# 9xVoice_MikeB_SMD_v1_0b.net
KiCad netlist of a schematic drawn in EAGLE
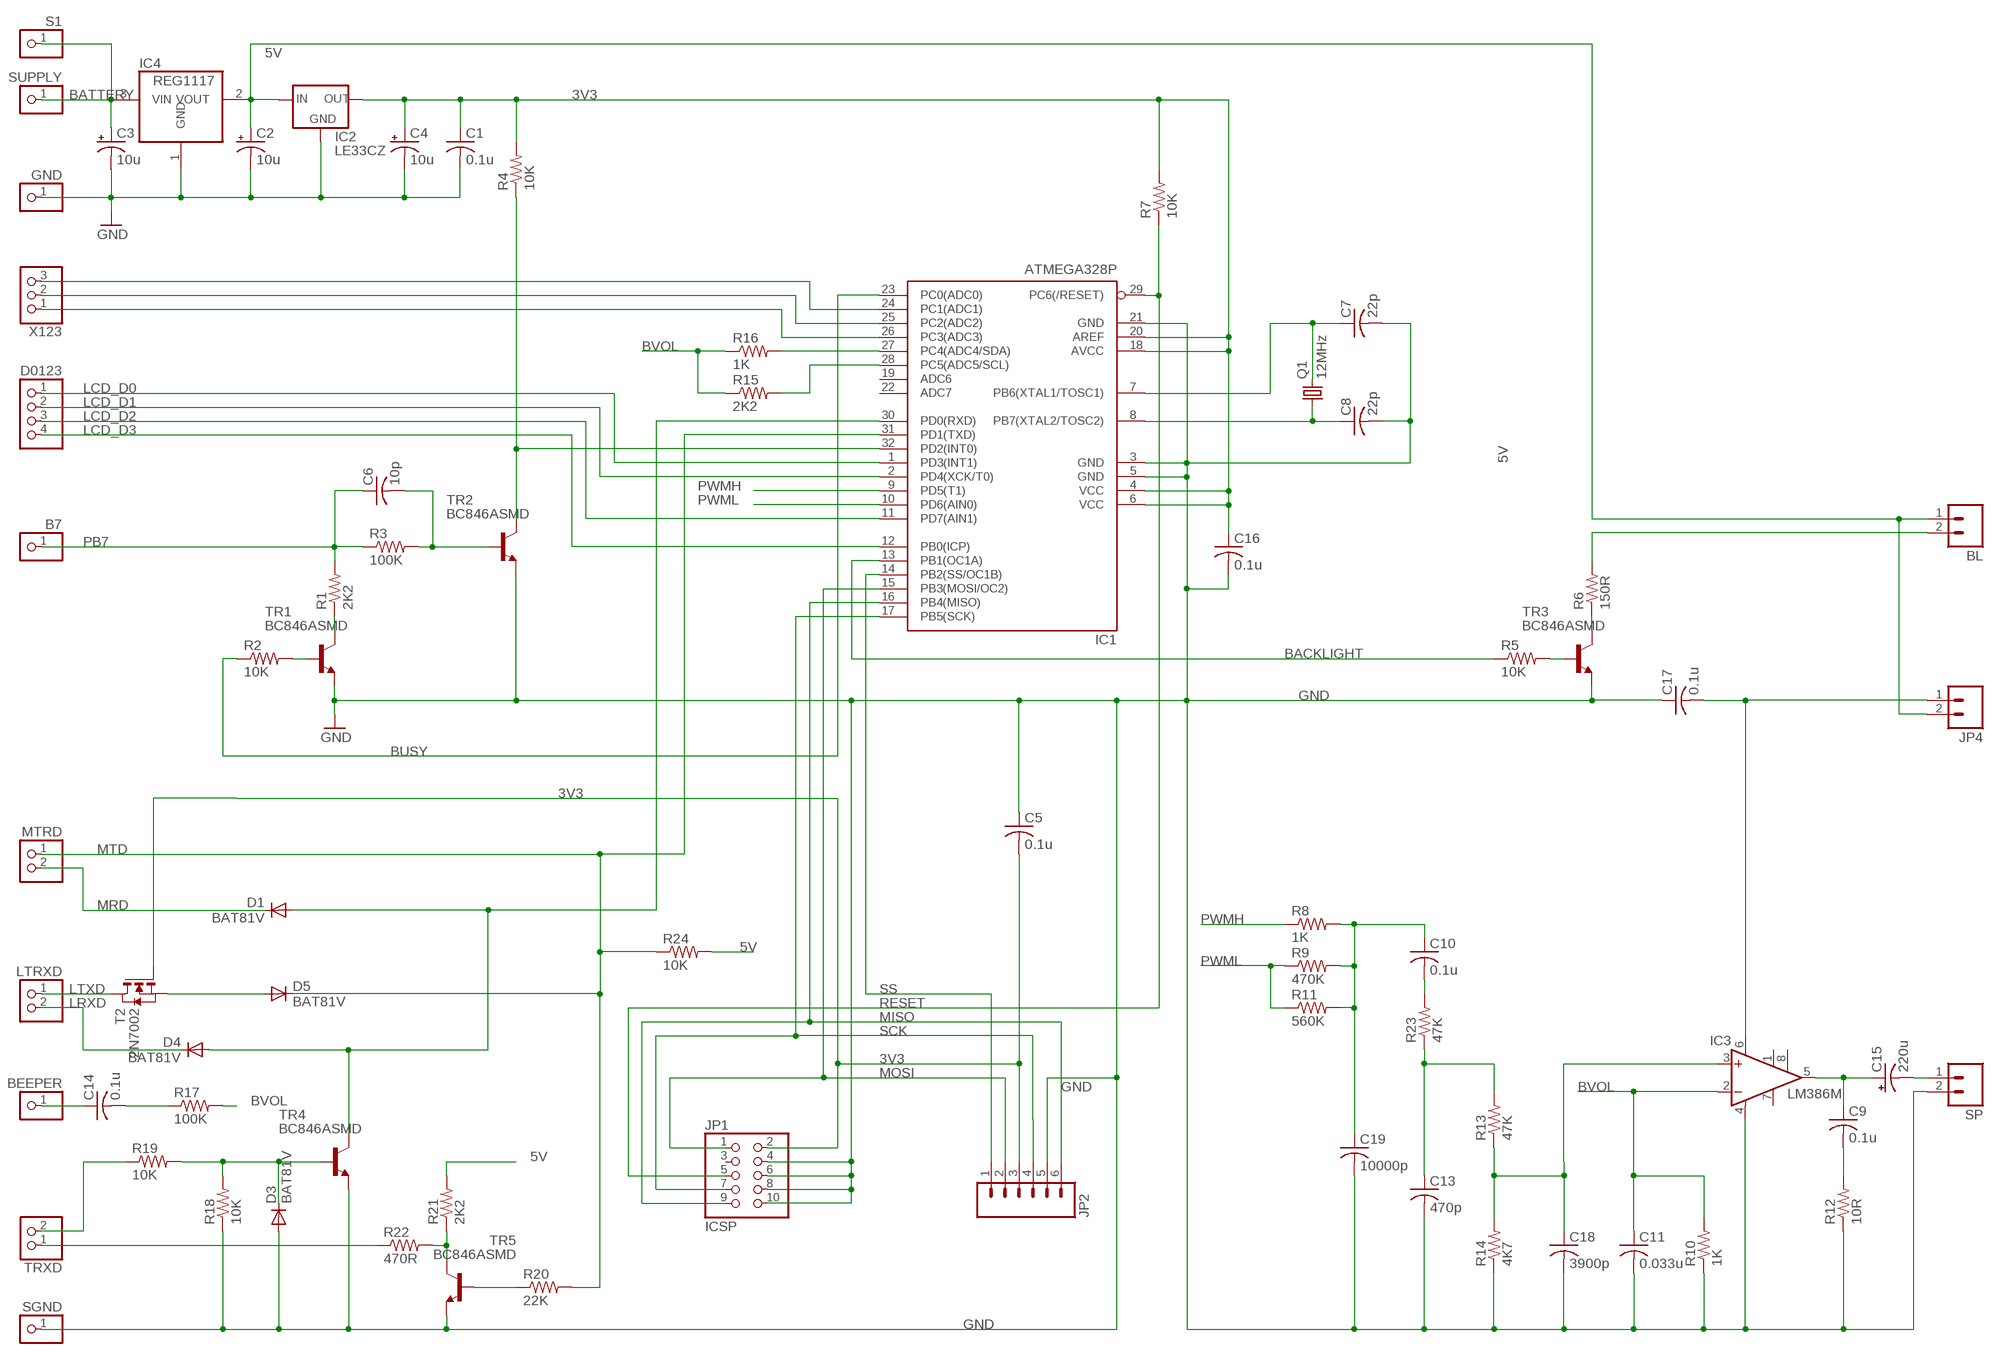
[diagram p0: schematic, sheet 1]

(export (version "E")
  (design (tool "Eeschema 10.0.6"))
  (components
    (comp (ref "B7")
      (value "PINHD-1X1")
      (footprint "eagle-import:1X01")
      (libsource (lib "eagle-import") (part "PINHD-1X1"))
    )
    (comp (ref "BEEPER")
      (value "PINHD-1X1")
      (footprint "eagle-import:1X01")
      (libsource (lib "eagle-import") (part "PINHD-1X1"))
    )
    (comp (ref "BL")
      (value "M02PTH")
      (footprint "eagle-import:1X02")
      (libsource (lib "eagle-import") (part "M02PTH"))
    )
    (comp (ref "C1")
      (value "0.1u")
      (footprint "eagle-import:C1206")
      (libsource (lib "eagle-import") (part "C-USC1206"))
    )
    (comp (ref "C2")
      (value "10u")
      (footprint "eagle-import:A_3216-18R")
      (libsource (lib "eagle-import") (part "CPOL-USA/3216-18R"))
    )
    (comp (ref "C3")
      (value "10u")
      (footprint "eagle-import:A_3216-18R")
      (libsource (lib "eagle-import") (part "CPOL-USA/3216-18R"))
    )
    (comp (ref "C4")
      (value "10u")
      (footprint "eagle-import:A_3216-18R")
      (libsource (lib "eagle-import") (part "CPOL-USA/3216-18R"))
    )
    (comp (ref "C5")
      (value "0.1u")
      (footprint "eagle-import:C1206")
      (libsource (lib "eagle-import") (part "C-USC1206"))
    )
    (comp (ref "C6")
      (value "10p")
      (footprint "eagle-import:C1206")
      (libsource (lib "eagle-import") (part "C-USC1206"))
    )
    (comp (ref "C7")
      (value "22p")
      (footprint "eagle-import:C1206")
      (libsource (lib "eagle-import") (part "C-USC1206"))
    )
    (comp (ref "C8")
      (value "22p")
      (footprint "eagle-import:C1206")
      (libsource (lib "eagle-import") (part "C-USC1206"))
    )
    (comp (ref "C9")
      (value "0.1u")
      (footprint "eagle-import:C1206")
      (libsource (lib "eagle-import") (part "C-USC1206"))
    )
    (comp (ref "C10")
      (value "0.1u")
      (footprint "eagle-import:C1206")
      (libsource (lib "eagle-import") (part "C-USC1206"))
    )
    (comp (ref "C11")
      (value "0.033u")
      (footprint "eagle-import:C1206")
      (libsource (lib "eagle-import") (part "C-USC1206"))
    )
    (comp (ref "C13")
      (value "470p")
      (footprint "eagle-import:C1206")
      (libsource (lib "eagle-import") (part "C-USC1206"))
    )
    (comp (ref "C14")
      (value "0.1u")
      (footprint "eagle-import:C1206")
      (libsource (lib "eagle-import") (part "C-USC1206"))
    )
    (comp (ref "C15")
      (value "220u")
      (footprint "eagle-import:CT7343")
      (libsource (lib "eagle-import") (part "CPOL-USCT7343"))
    )
    (comp (ref "C16")
      (value "0.1u")
      (footprint "eagle-import:C1206")
      (libsource (lib "eagle-import") (part "C-USC1206"))
    )
    (comp (ref "C17")
      (value "0.1u")
      (footprint "eagle-import:C1206")
      (libsource (lib "eagle-import") (part "C-USC1206"))
    )
    (comp (ref "C18")
      (value "3900p")
      (footprint "eagle-import:C1206")
      (libsource (lib "eagle-import") (part "C-USC1206"))
    )
    (comp (ref "C19")
      (value "10000p")
      (footprint "eagle-import:C1206")
      (libsource (lib "eagle-import") (part "C-USC1206"))
    )
    (comp (ref "D1")
      (value "BAT81V")
      (footprint "eagle-import:SOD123")
      (libsource (lib "eagle-import") (part "DIODE-SOD123"))
    )
    (comp (ref "D3")
      (value "BAT81V")
      (footprint "eagle-import:SOD123")
      (libsource (lib "eagle-import") (part "DIODE-SOD123"))
    )
    (comp (ref "D4")
      (value "BAT81V")
      (footprint "eagle-import:SOD123")
      (libsource (lib "eagle-import") (part "DIODE-SOD123"))
    )
    (comp (ref "D5")
      (value "BAT81V")
      (footprint "eagle-import:SOD123")
      (libsource (lib "eagle-import") (part "DIODE-SOD123"))
    )
    (comp (ref "D0123")
      (value "PINHD-1X4")
      (footprint "eagle-import:1X04")
      (libsource (lib "eagle-import") (part "PINHD-1X4"))
    )
    (comp (ref "GND")
      (value "PINHD-1X1")
      (footprint "eagle-import:1X01")
      (libsource (lib "eagle-import") (part "PINHD-1X1"))
    )
    (comp (ref "IC1")
      (value "ATMEGA328P")
      (footprint "eagle-import:TQFP32-08")
      (fields
        (field (name "MPN") "ATMEGA8-16AU")
        (field (name "MPN_1") "ATMEGA8-16AU")
        (field (name "OC_FARNELL") "9171371")
        (field (name "OC_NEWARK") "73M8863")
      )
      (libsource (lib "eagle-import") (part "MEGA8-AI"))
    )
    (comp (ref "IC2")
      (value "LE33CZ")
      (footprint "eagle-import:SOT23")
      (libsource (lib "eagle-import") (part "XC63FPM"))
    )
    (comp (ref "IC3")
      (value "LM386M")
      (footprint "eagle-import:SO08")
      (libsource (lib "eagle-import") (part "LM386?-M1"))
    )
    (comp (ref "IC4")
      (value "REG1117")
      (footprint "eagle-import:SOT223")
      (libsource (lib "eagle-import") (part "REG1117"))
    )
    (comp (ref "JP1")
      (value "ICSP")
      (footprint "eagle-import:2X05")
      (libsource (lib "eagle-import") (part "PINHD-2X5"))
    )
    (comp (ref "JP2")
      (value "M06SIP")
      (footprint "eagle-import:1X06")
      (libsource (lib "eagle-import") (part "M06SIP"))
    )
    (comp (ref "JP4")
      (value "M02PTH")
      (footprint "eagle-import:1X02")
      (libsource (lib "eagle-import") (part "M02PTH"))
    )
    (comp (ref "LTRXD")
      (value "PINHD-1X2")
      (footprint "eagle-import:1X02")
      (libsource (lib "eagle-import") (part "PINHD-1X2"))
    )
    (comp (ref "MTRD")
      (value "PINHD-1X2")
      (footprint "eagle-import:1X02")
      (libsource (lib "eagle-import") (part "PINHD-1X2"))
    )
    (comp (ref "Q1")
      (value "12MHz")
      (footprint "eagle-import:2-SMD")
      (libsource (lib "eagle-import") (part "7A"))
    )
    (comp (ref "R1")
      (value "2K2")
      (footprint "eagle-import:R1206")
      (libsource (lib "eagle-import") (part "R-US_R1206"))
    )
    (comp (ref "R2")
      (value "10K")
      (footprint "eagle-import:R1206")
      (libsource (lib "eagle-import") (part "R-US_R1206"))
    )
    (comp (ref "R3")
      (value "100K")
      (footprint "eagle-import:R1206")
      (libsource (lib "eagle-import") (part "R-US_R1206"))
    )
    (comp (ref "R4")
      (value "10K")
      (footprint "eagle-import:R1206")
      (libsource (lib "eagle-import") (part "R-US_R1206"))
    )
    (comp (ref "R5")
      (value "10K")
      (footprint "eagle-import:R1206")
      (libsource (lib "eagle-import") (part "R-US_R1206"))
    )
    (comp (ref "R6")
      (value "150R")
      (footprint "eagle-import:R1206")
      (libsource (lib "eagle-import") (part "R-US_R1206"))
    )
    (comp (ref "R7")
      (value "10K")
      (footprint "eagle-import:R1206")
      (libsource (lib "eagle-import") (part "R-US_R1206"))
    )
    (comp (ref "R8")
      (value "1K")
      (footprint "eagle-import:R1206")
      (libsource (lib "eagle-import") (part "R-US_R1206"))
    )
    (comp (ref "R9")
      (value "470K")
      (footprint "eagle-import:R1206")
      (libsource (lib "eagle-import") (part "R-US_R1206"))
    )
    (comp (ref "R10")
      (value "1K")
      (footprint "eagle-import:R1206")
      (libsource (lib "eagle-import") (part "R-US_R1206"))
    )
    (comp (ref "R11")
      (value "560K")
      (footprint "eagle-import:R1206")
      (libsource (lib "eagle-import") (part "R-US_R1206"))
    )
    (comp (ref "R12")
      (value "10R")
      (footprint "eagle-import:R1206")
      (libsource (lib "eagle-import") (part "R-US_R1206"))
    )
    (comp (ref "R13")
      (value "47K")
      (footprint "eagle-import:R1206")
      (libsource (lib "eagle-import") (part "R-US_R1206"))
    )
    (comp (ref "R14")
      (value "4K7")
      (footprint "eagle-import:R1206")
      (libsource (lib "eagle-import") (part "R-US_R1206"))
    )
    (comp (ref "R15")
      (value "2K2")
      (footprint "eagle-import:R1206")
      (libsource (lib "eagle-import") (part "R-US_R1206"))
    )
    (comp (ref "R16")
      (value "1K")
      (footprint "eagle-import:R1206")
      (libsource (lib "eagle-import") (part "R-US_R1206"))
    )
    (comp (ref "R17")
      (value "100K")
      (footprint "eagle-import:R1206")
      (libsource (lib "eagle-import") (part "R-US_R1206"))
    )
    (comp (ref "R18")
      (value "10K")
      (footprint "eagle-import:R1206")
      (libsource (lib "eagle-import") (part "R-US_R1206"))
    )
    (comp (ref "R19")
      (value "10K")
      (footprint "eagle-import:R1206")
      (libsource (lib "eagle-import") (part "R-US_R1206"))
    )
    (comp (ref "R20")
      (value "22K")
      (footprint "eagle-import:R1206")
      (libsource (lib "eagle-import") (part "R-US_R1206"))
    )
    (comp (ref "R21")
      (value "2K2")
      (footprint "eagle-import:R1206")
      (libsource (lib "eagle-import") (part "R-US_R1206"))
    )
    (comp (ref "R22")
      (value "470R")
      (footprint "eagle-import:R1206")
      (libsource (lib "eagle-import") (part "R-US_R1206"))
    )
    (comp (ref "R23")
      (value "47K")
      (footprint "eagle-import:R1206")
      (libsource (lib "eagle-import") (part "R-US_R1206"))
    )
    (comp (ref "R24")
      (value "10K")
      (footprint "eagle-import:R1206")
      (libsource (lib "eagle-import") (part "R-US_R1206"))
    )
    (comp (ref "S1")
      (value "PINHD-1X1")
      (footprint "eagle-import:1X01")
      (libsource (lib "eagle-import") (part "PINHD-1X1"))
    )
    (comp (ref "SGND")
      (value "PINHD-1X1")
      (footprint "eagle-import:1X01")
      (libsource (lib "eagle-import") (part "PINHD-1X1"))
    )
    (comp (ref "SP")
      (value "M02PTH")
      (footprint "eagle-import:1X02")
      (libsource (lib "eagle-import") (part "M02PTH"))
    )
    (comp (ref "SUPPLY")
      (value "PINHD-1X1")
      (footprint "eagle-import:1X01")
      (libsource (lib "eagle-import") (part "PINHD-1X1"))
    )
    (comp (ref "T2")
      (value "2N7002")
      (footprint "eagle-import:SOT-23")
      (libsource (lib "eagle-import") (part "NMOSSOT23"))
    )
    (comp (ref "TR1")
      (value "BC846ASMD")
      (footprint "eagle-import:SOT23")
      (libsource (lib "eagle-import") (part "BC846SMDA"))
    )
    (comp (ref "TR2")
      (value "BC846ASMD")
      (footprint "eagle-import:SOT23")
      (libsource (lib "eagle-import") (part "BC846SMDA"))
    )
    (comp (ref "TR3")
      (value "BC846ASMD")
      (footprint "eagle-import:SOT23")
      (libsource (lib "eagle-import") (part "BC846SMDA"))
    )
    (comp (ref "TR4")
      (value "BC846ASMD")
      (footprint "eagle-import:SOT23")
      (libsource (lib "eagle-import") (part "BC846SMDA"))
    )
    (comp (ref "TR5")
      (value "BC846ASMD")
      (footprint "eagle-import:SOT23")
      (libsource (lib "eagle-import") (part "BC846SMDA"))
    )
    (comp (ref "TRXD")
      (value "PINHD-1X2")
      (footprint "eagle-import:1X02")
      (libsource (lib "eagle-import") (part "PINHD-1X2"))
    )
    (comp (ref "X123")
      (value "PINHD-1X3")
      (footprint "eagle-import:1X03")
      (libsource (lib "eagle-import") (part "PINHD-1X3"))
    )
  )
  (nets
    (net (code "1") (name "/3V3") (class "Default")
      (node (ref "C1") (pin "1") (pinfunction "1_1") (pintype "passive"))
      (node (ref "C16") (pin "1") (pinfunction "1_1") (pintype "passive"))
      (node (ref "C4") (pin "+") (pinfunction "+_+") (pintype "passive"))
      (node (ref "C5") (pin "2") (pinfunction "2_2") (pintype "passive"))
      (node (ref "IC1") (pin "18") (pinfunction "AVCC_18") (pintype "power_in"))
      (node (ref "IC1") (pin "20") (pinfunction "AREF_20") (pintype "passive"))
      (node (ref "IC1") (pin "4") (pinfunction "VCC_4") (pintype "power_in"))
      (node (ref "IC1") (pin "6") (pinfunction "VCC_6") (pintype "power_in"))
      (node (ref "IC2") (pin "2") (pinfunction "OUT_2") (pintype "passive"))
      (node (ref "JP1") (pin "2") (pinfunction "2_2") (pintype "passive"))
      (node (ref "JP2") (pin "3") (pinfunction "3_3") (pintype "passive"))
      (node (ref "R4") (pin "2") (pinfunction "2_2") (pintype "passive"))
      (node (ref "R7") (pin "2") (pinfunction "2_2") (pintype "passive"))
      (node (ref "T2") (pin "3") (pinfunction "G_3") (pintype "passive"))
    )
    (net (code "2") (name "/5V") (class "Default")
      (node (ref "BL") (pin "1") (pinfunction "1_1") (pintype "passive"))
      (node (ref "C2") (pin "+") (pinfunction "+_+") (pintype "passive"))
      (node (ref "IC2") (pin "3") (pinfunction "IN_3") (pintype "input"))
      (node (ref "IC4") (pin "2") (pinfunction "VOUT_2") (pintype "output"))
      (node (ref "JP4") (pin "2") (pinfunction "2_2") (pintype "passive"))
      (node (ref "R21") (pin "2") (pinfunction "2_2") (pintype "passive"))
      (node (ref "R24") (pin "2") (pinfunction "2_2") (pintype "passive"))
    )
    (net (code "3") (name "/BACKLIGHT") (class "Default")
      (node (ref "IC1") (pin "13") (pinfunction "PB1(OC1A)_13") (pintype "bidirectional"))
      (node (ref "R5") (pin "1") (pinfunction "1_1") (pintype "passive"))
    )
    (net (code "4") (name "/BATTERY") (class "Default")
      (node (ref "C3") (pin "+") (pinfunction "+_+") (pintype "passive"))
      (node (ref "IC4") (pin "3") (pinfunction "VIN_3") (pintype "input"))
      (node (ref "S1") (pin "1") (pinfunction "1_1") (pintype "passive"))
      (node (ref "SUPPLY") (pin "1") (pinfunction "1_1") (pintype "passive"))
    )
    (net (code "5") (name "/BUSY") (class "Default")
      (node (ref "IC1") (pin "23") (pinfunction "PC0(ADC0)_23") (pintype "bidirectional"))
      (node (ref "R2") (pin "1") (pinfunction "1_1") (pintype "passive"))
    )
    (net (code "6") (name "/BVOL") (class "Default")
      (node (ref "C11") (pin "1") (pinfunction "1_1") (pintype "passive"))
      (node (ref "IC3") (pin "2") (pinfunction "-IN_2") (pintype "input"))
      (node (ref "R10") (pin "2") (pinfunction "2_2") (pintype "passive"))
      (node (ref "R15") (pin "1") (pinfunction "1_1") (pintype "passive"))
      (node (ref "R16") (pin "1") (pinfunction "1_1") (pintype "passive"))
      (node (ref "R17") (pin "2") (pinfunction "2_2") (pintype "passive"))
    )
    (net (code "7") (name "/LCD_D0") (class "Default")
      (node (ref "D0123") (pin "1") (pinfunction "1_1") (pintype "passive"))
      (node (ref "IC1") (pin "1") (pinfunction "PD3(INT1)_1") (pintype "bidirectional"))
    )
    (net (code "8") (name "/LCD_D1") (class "Default")
      (node (ref "D0123") (pin "2") (pinfunction "2_2") (pintype "passive"))
      (node (ref "IC1") (pin "2") (pinfunction "PD4(XCK/T0)_2") (pintype "bidirectional"))
    )
    (net (code "9") (name "/LCD_D2") (class "Default")
      (node (ref "D0123") (pin "3") (pinfunction "3_3") (pintype "passive"))
      (node (ref "IC1") (pin "11") (pinfunction "PD7(AIN1)_11") (pintype "bidirectional"))
    )
    (net (code "10") (name "/LCD_D3") (class "Default")
      (node (ref "D0123") (pin "4") (pinfunction "4_4") (pintype "passive"))
      (node (ref "IC1") (pin "12") (pinfunction "PB0(ICP)_12") (pintype "bidirectional"))
    )
    (net (code "11") (name "/LRXD") (class "Default")
      (node (ref "D4") (pin "C") (pinfunction "C_C") (pintype "passive"))
      (node (ref "LTRXD") (pin "2") (pinfunction "2_2") (pintype "passive"))
    )
    (net (code "12") (name "/LTXD") (class "Default")
      (node (ref "LTRXD") (pin "1") (pinfunction "1_1") (pintype "passive"))
      (node (ref "T2") (pin "1") (pinfunction "D_1") (pintype "passive"))
    )
    (net (code "13") (name "/MISO") (class "Default")
      (node (ref "IC1") (pin "16") (pinfunction "PB4(MISO)_16") (pintype "bidirectional"))
      (node (ref "JP1") (pin "9") (pinfunction "9_9") (pintype "passive"))
      (node (ref "JP2") (pin "6") (pinfunction "6_6") (pintype "passive"))
    )
    (net (code "14") (name "/MOSI") (class "Default")
      (node (ref "IC1") (pin "15") (pinfunction "PB3(MOSI/OC2)_15") (pintype "bidirectional"))
      (node (ref "JP1") (pin "1") (pinfunction "1_1") (pintype "passive"))
      (node (ref "JP2") (pin "2") (pinfunction "2_2") (pintype "passive"))
    )
    (net (code "15") (name "/MRD") (class "Default")
      (node (ref "D1") (pin "C") (pinfunction "C_C") (pintype "passive"))
      (node (ref "MTRD") (pin "2") (pinfunction "2_2") (pintype "passive"))
    )
    (net (code "16") (name "/MTD") (class "Default")
      (node (ref "D5") (pin "C") (pinfunction "C_C") (pintype "passive"))
      (node (ref "IC1") (pin "31") (pinfunction "PD1(TXD)_31") (pintype "bidirectional"))
      (node (ref "MTRD") (pin "1") (pinfunction "1_1") (pintype "passive"))
      (node (ref "R20") (pin "2") (pinfunction "2_2") (pintype "passive"))
      (node (ref "R24") (pin "1") (pinfunction "1_1") (pintype "passive"))
    )
    (net (code "17") (name "/PB7") (class "Default")
      (node (ref "B7") (pin "1") (pinfunction "1_1") (pintype "passive"))
      (node (ref "C6") (pin "1") (pinfunction "1_1") (pintype "passive"))
      (node (ref "R1") (pin "2") (pinfunction "2_2") (pintype "passive"))
      (node (ref "R3") (pin "1") (pinfunction "1_1") (pintype "passive"))
    )
    (net (code "18") (name "/PWMH") (class "Default")
      (node (ref "IC1") (pin "9") (pinfunction "PD5(T1)_9") (pintype "bidirectional"))
      (node (ref "R8") (pin "1") (pinfunction "1_1") (pintype "passive"))
    )
    (net (code "19") (name "/PWML") (class "Default")
      (node (ref "IC1") (pin "10") (pinfunction "PD6(AIN0)_10") (pintype "bidirectional"))
      (node (ref "R11") (pin "1") (pinfunction "1_1") (pintype "passive"))
      (node (ref "R9") (pin "1") (pinfunction "1_1") (pintype "passive"))
    )
    (net (code "20") (name "/RESET") (class "Default")
      (node (ref "IC1") (pin "29") (pinfunction "PC6(/RESET)_29") (pintype "bidirectional"))
      (node (ref "JP1") (pin "5") (pinfunction "5_5") (pintype "passive"))
      (node (ref "R7") (pin "1") (pinfunction "1_1") (pintype "passive"))
    )
    (net (code "21") (name "/SCK") (class "Default")
      (node (ref "IC1") (pin "17") (pinfunction "PB5(SCK)_17") (pintype "bidirectional"))
      (node (ref "JP1") (pin "7") (pinfunction "7_7") (pintype "passive"))
      (node (ref "JP2") (pin "4") (pinfunction "4_4") (pintype "passive"))
    )
    (net (code "22") (name "/SS") (class "Default")
      (node (ref "IC1") (pin "14") (pinfunction "PB2(SS/OC1B)_14") (pintype "bidirectional"))
      (node (ref "JP2") (pin "1") (pinfunction "1_1") (pintype "passive"))
    )
    (net (code "23") (name "GND") (class "Default")
      (node (ref "C1") (pin "2") (pinfunction "2_2") (pintype "passive"))
      (node (ref "C11") (pin "2") (pinfunction "2_2") (pintype "passive"))
      (node (ref "C13") (pin "2") (pinfunction "2_2") (pintype "passive"))
      (node (ref "C16") (pin "2") (pinfunction "2_2") (pintype "passive"))
      (node (ref "C17") (pin "1") (pinfunction "1_1") (pintype "passive"))
      (node (ref "C18") (pin "2") (pinfunction "2_2") (pintype "passive"))
      (node (ref "C19") (pin "2") (pinfunction "2_2") (pintype "passive"))
      (node (ref "C2") (pin "-") (pinfunction "-_-") (pintype "passive"))
      (node (ref "C3") (pin "-") (pinfunction "-_-") (pintype "passive"))
      (node (ref "C4") (pin "-") (pinfunction "-_-") (pintype "passive"))
      (node (ref "C5") (pin "1") (pinfunction "1_1") (pintype "passive"))
      (node (ref "C7") (pin "2") (pinfunction "2_2") (pintype "passive"))
      (node (ref "C8") (pin "2") (pinfunction "2_2") (pintype "passive"))
      (node (ref "D3") (pin "A") (pinfunction "A_A") (pintype "passive"))
      (node (ref "GND") (pin "1") (pinfunction "1_1") (pintype "passive"))
      (node (ref "IC1") (pin "21") (pinfunction "GND_21") (pintype "power_in"))
      (node (ref "IC1") (pin "3") (pinfunction "GND_3") (pintype "power_in"))
      (node (ref "IC1") (pin "5") (pinfunction "GND_5") (pintype "power_in"))
      (node (ref "IC2") (pin "1") (pinfunction "GND_1") (pintype "input"))
      (node (ref "IC3") (pin "4") (pinfunction "GND_4") (pintype "power_in"))
      (node (ref "IC4") (pin "1") (pinfunction "GND_1") (pintype "power_in"))
      (node (ref "JP1") (pin "10") (pinfunction "10_10") (pintype "passive"))
      (node (ref "JP1") (pin "4") (pinfunction "4_4") (pintype "passive"))
      (node (ref "JP1") (pin "6") (pinfunction "6_6") (pintype "passive"))
      (node (ref "JP1") (pin "8") (pinfunction "8_8") (pintype "passive"))
      (node (ref "JP2") (pin "5") (pinfunction "5_5") (pintype "passive"))
      (node (ref "R10") (pin "1") (pinfunction "1_1") (pintype "passive"))
      (node (ref "R12") (pin "1") (pinfunction "1_1") (pintype "passive"))
      (node (ref "R14") (pin "1") (pinfunction "1_1") (pintype "passive"))
      (node (ref "R18") (pin "1") (pinfunction "1_1") (pintype "passive"))
      (node (ref "SGND") (pin "1") (pinfunction "1_1") (pintype "passive"))
      (node (ref "SP") (pin "2") (pinfunction "2_2") (pintype "passive"))
      (node (ref "TR1") (pin "2") (pinfunction "E_2") (pintype "passive"))
      (node (ref "TR2") (pin "2") (pinfunction "E_2") (pintype "passive"))
      (node (ref "TR3") (pin "2") (pinfunction "E_2") (pintype "passive"))
      (node (ref "TR4") (pin "2") (pinfunction "E_2") (pintype "passive"))
      (node (ref "TR5") (pin "2") (pinfunction "E_2") (pintype "passive"))
    )
    (net (code "24") (name "Net-(BEEPER-Pad1)") (class "Default")
      (node (ref "BEEPER") (pin "1") (pinfunction "1_1") (pintype "passive"))
      (node (ref "C14") (pin "1") (pinfunction "1_1") (pintype "passive"))
    )
    (net (code "25") (name "Net-(BL-Pad2)") (class "Default")
      (node (ref "BL") (pin "2") (pinfunction "2_2") (pintype "passive"))
      (node (ref "R6") (pin "2") (pinfunction "2_2") (pintype "passive"))
    )
    (net (code "26") (name "Net-(C9-Pad2)") (class "Default")
      (node (ref "C9") (pin "2") (pinfunction "2_2") (pintype "passive"))
      (node (ref "R12") (pin "2") (pinfunction "2_2") (pintype "passive"))
    )
    (net (code "27") (name "Net-(C10-Pad1)") (class "Default")
      (node (ref "C10") (pin "1") (pinfunction "1_1") (pintype "passive"))
      (node (ref "C19") (pin "1") (pinfunction "1_1") (pintype "passive"))
      (node (ref "R11") (pin "2") (pinfunction "2_2") (pintype "passive"))
      (node (ref "R8") (pin "2") (pinfunction "2_2") (pintype "passive"))
      (node (ref "R9") (pin "2") (pinfunction "2_2") (pintype "passive"))
    )
    (net (code "28") (name "Net-(C10-Pad2)") (class "Default")
      (node (ref "C10") (pin "2") (pinfunction "2_2") (pintype "passive"))
      (node (ref "R23") (pin "2") (pinfunction "2_2") (pintype "passive"))
    )
    (net (code "29") (name "Net-(C13-Pad1)") (class "Default")
      (node (ref "C13") (pin "1") (pinfunction "1_1") (pintype "passive"))
      (node (ref "R13") (pin "2") (pinfunction "2_2") (pintype "passive"))
      (node (ref "R23") (pin "1") (pinfunction "1_1") (pintype "passive"))
    )
    (net (code "30") (name "Net-(C14-Pad2)") (class "Default")
      (node (ref "C14") (pin "2") (pinfunction "2_2") (pintype "passive"))
      (node (ref "R17") (pin "1") (pinfunction "1_1") (pintype "passive"))
    )
    (net (code "31") (name "Net-(C15-Pad-)") (class "Default")
      (node (ref "C15") (pin "-") (pinfunction "-_-") (pintype "passive"))
      (node (ref "SP") (pin "1") (pinfunction "1_1") (pintype "passive"))
    )
    (net (code "32") (name "Net-(IC1-PB6(XTAL1{slash}TOSC1))") (class "Default")
      (node (ref "C7") (pin "1") (pinfunction "1_1") (pintype "passive"))
      (node (ref "IC1") (pin "7") (pinfunction "PB6(XTAL1/TOSC1)_7") (pintype "bidirectional"))
      (node (ref "Q1") (pin "P$2") (pinfunction "2_P$2") (pintype "passive"))
    )
    (net (code "33") (name "Net-(IC1-PB7(XTAL2{slash}TOSC2))") (class "Default")
      (node (ref "C8") (pin "1") (pinfunction "1_1") (pintype "passive"))
      (node (ref "IC1") (pin "8") (pinfunction "PB7(XTAL2/TOSC2)_8") (pintype "bidirectional"))
      (node (ref "Q1") (pin "P$1") (pinfunction "1_P$1") (pintype "passive"))
    )
    (net (code "34") (name "Net-(IC1-PC1(ADC1))") (class "Default")
      (node (ref "IC1") (pin "24") (pinfunction "PC1(ADC1)_24") (pintype "bidirectional"))
      (node (ref "X123") (pin "3") (pinfunction "3_3") (pintype "passive"))
    )
    (net (code "35") (name "Net-(IC1-PC2(ADC2))") (class "Default")
      (node (ref "IC1") (pin "25") (pinfunction "PC2(ADC2)_25") (pintype "bidirectional"))
      (node (ref "X123") (pin "2") (pinfunction "2_2") (pintype "passive"))
    )
    (net (code "36") (name "Net-(IC1-PC3(ADC3))") (class "Default")
      (node (ref "IC1") (pin "26") (pinfunction "PC3(ADC3)_26") (pintype "bidirectional"))
      (node (ref "X123") (pin "1") (pinfunction "1_1") (pintype "passive"))
    )
    (net (code "37") (name "Net-(IC1-PC4(ADC4{slash}SDA))") (class "Default")
      (node (ref "IC1") (pin "27") (pinfunction "PC4(ADC4/SDA)_27") (pintype "bidirectional"))
      (node (ref "R16") (pin "2") (pinfunction "2_2") (pintype "passive"))
    )
    (net (code "38") (name "Net-(IC1-PC5(ADC5{slash}SCL))") (class "Default")
      (node (ref "IC1") (pin "28") (pinfunction "PC5(ADC5/SCL)_28") (pintype "bidirectional"))
      (node (ref "R15") (pin "2") (pinfunction "2_2") (pintype "passive"))
    )
    (net (code "39") (name "Net-(IC1-PD0(RXD))") (class "Default")
      (node (ref "D1") (pin "A") (pinfunction "A_A") (pintype "passive"))
      (node (ref "D4") (pin "A") (pinfunction "A_A") (pintype "passive"))
      (node (ref "IC1") (pin "30") (pinfunction "PD0(RXD)_30") (pintype "bidirectional"))
      (node (ref "TR4") (pin "3") (pinfunction "C_3") (pintype "passive"))
    )
    (net (code "40") (name "Net-(IC1-PD2(INT0))") (class "Default")
      (node (ref "IC1") (pin "32") (pinfunction "PD2(INT0)_32") (pintype "bidirectional"))
      (node (ref "R4") (pin "1") (pinfunction "1_1") (pintype "passive"))
      (node (ref "TR2") (pin "3") (pinfunction "C_3") (pintype "passive"))
    )
    (net (code "41") (name "Net-(IC3-+IN)") (class "Default")
      (node (ref "C18") (pin "1") (pinfunction "1_1") (pintype "passive"))
      (node (ref "IC3") (pin "3") (pinfunction "+IN_3") (pintype "input"))
      (node (ref "R13") (pin "1") (pinfunction "1_1") (pintype "passive"))
      (node (ref "R14") (pin "2") (pinfunction "2_2") (pintype "passive"))
    )
    (net (code "42") (name "Net-(IC3-OUT)") (class "Default")
      (node (ref "C15") (pin "+") (pinfunction "+_+") (pintype "passive"))
      (node (ref "C9") (pin "1") (pinfunction "1_1") (pintype "passive"))
      (node (ref "IC3") (pin "5") (pinfunction "OUT_5") (pintype "output"))
    )
    (net (code "43") (name "Net-(IC3-VS)") (class "Default")
      (node (ref "C17") (pin "2") (pinfunction "2_2") (pintype "passive"))
      (node (ref "IC3") (pin "6") (pinfunction "VS_6") (pintype "power_in"))
      (node (ref "JP4") (pin "1") (pinfunction "1_1") (pintype "passive"))
    )
    (net (code "44") (name "Net-(R19-Pad1)") (class "Default")
      (node (ref "R19") (pin "1") (pinfunction "1_1") (pintype "passive"))
      (node (ref "TRXD") (pin "2") (pinfunction "2_2") (pintype "passive"))
    )
    (net (code "45") (name "Net-(R22-Pad1)") (class "Default")
      (node (ref "R22") (pin "1") (pinfunction "1_1") (pintype "passive"))
      (node (ref "TRXD") (pin "1") (pinfunction "1_1") (pintype "passive"))
    )
    (net (code "46") (name "Net-(T2-S)") (class "Default")
      (node (ref "D5") (pin "A") (pinfunction "A_A") (pintype "passive"))
      (node (ref "T2") (pin "2") (pinfunction "S_2") (pintype "passive"))
    )
    (net (code "47") (name "Net-(TR1-B)") (class "Default")
      (node (ref "R2") (pin "2") (pinfunction "2_2") (pintype "passive"))
      (node (ref "TR1") (pin "1") (pinfunction "B_1") (pintype "passive"))
    )
    (net (code "48") (name "Net-(TR1-C)") (class "Default")
      (node (ref "R1") (pin "1") (pinfunction "1_1") (pintype "passive"))
      (node (ref "TR1") (pin "3") (pinfunction "C_3") (pintype "passive"))
    )
    (net (code "49") (name "Net-(TR2-B)") (class "Default")
      (node (ref "C6") (pin "2") (pinfunction "2_2") (pintype "passive"))
      (node (ref "R3") (pin "2") (pinfunction "2_2") (pintype "passive"))
      (node (ref "TR2") (pin "1") (pinfunction "B_1") (pintype "passive"))
    )
    (net (code "50") (name "Net-(TR3-B)") (class "Default")
      (node (ref "R5") (pin "2") (pinfunction "2_2") (pintype "passive"))
      (node (ref "TR3") (pin "1") (pinfunction "B_1") (pintype "passive"))
    )
    (net (code "51") (name "Net-(TR3-C)") (class "Default")
      (node (ref "R6") (pin "1") (pinfunction "1_1") (pintype "passive"))
      (node (ref "TR3") (pin "3") (pinfunction "C_3") (pintype "passive"))
    )
    (net (code "52") (name "Net-(TR4-B)") (class "Default")
      (node (ref "D3") (pin "C") (pinfunction "C_C") (pintype "passive"))
      (node (ref "R18") (pin "2") (pinfunction "2_2") (pintype "passive"))
      (node (ref "R19") (pin "2") (pinfunction "2_2") (pintype "passive"))
      (node (ref "TR4") (pin "1") (pinfunction "B_1") (pintype "passive"))
    )
    (net (code "53") (name "Net-(TR5-B)") (class "Default")
      (node (ref "R20") (pin "1") (pinfunction "1_1") (pintype "passive"))
      (node (ref "TR5") (pin "1") (pinfunction "B_1") (pintype "passive"))
    )
    (net (code "54") (name "Net-(TR5-C)") (class "Default")
      (node (ref "R21") (pin "1") (pinfunction "1_1") (pintype "passive"))
      (node (ref "R22") (pin "2") (pinfunction "2_2") (pintype "passive"))
      (node (ref "TR5") (pin "3") (pinfunction "C_3") (pintype "passive"))
    )
    (net (code "55") (name "unconnected-(IC1-ADC6-Pad19)") (class "Default")
      (node (ref "IC1") (pin "19") (pinfunction "ADC6_19") (pintype "bidirectional"))
    )
    (net (code "56") (name "unconnected-(IC1-ADC7-Pad22)") (class "Default")
      (node (ref "IC1") (pin "22") (pinfunction "ADC7_22") (pintype "bidirectional"))
    )
    (net (code "57") (name "unconnected-(IC3-BYPASS-Pad7)") (class "Default")
      (node (ref "IC3") (pin "7") (pinfunction "BYPASS_7") (pintype "passive"))
    )
    (net (code "58") (name "unconnected-(IC3-GAIN-Pad1)") (class "Default")
      (node (ref "IC3") (pin "1") (pinfunction "GAIN_1") (pintype "passive"))
    )
    (net (code "59") (name "unconnected-(IC3-GAIN-Pad8)") (class "Default")
      (node (ref "IC3") (pin "8") (pinfunction "GAIN_8") (pintype "passive"))
    )
    (net (code "60") (name "unconnected-(JP1-Pad3)") (class "Default")
      (node (ref "JP1") (pin "3") (pinfunction "3_3") (pintype "passive"))
    )
  )
)
